# BTM7752.net
KiCad netlist of a schematic drawn in EAGLE
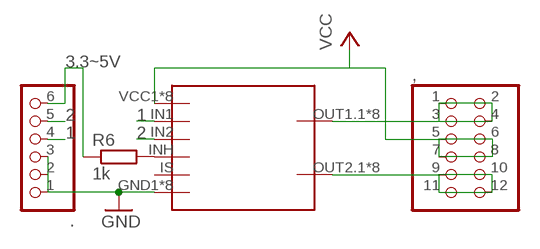
[diagram p0: schematic, sheet 1]

(export (version "E")
  (design (tool "Eeschema 10.0.6"))
  (components
    (comp (ref ",")
      (value "PINHD-2X6")
      (footprint "eagle-import:2X06")
      (libsource (lib "eagle-import") (part "PINHD-2X6"))
    )
    (comp (ref ".")
      (value "PINHD-1X6")
      (footprint "eagle-import:1X06")
      (libsource (lib "eagle-import") (part "PINHD-1X6"))
    )
    (comp (ref "R6")
      (value "1k")
      (footprint "eagle-import:R0603")
      (libsource (lib "eagle-import") (part "R-EU_R0603"))
    )
    (comp (ref "U$1")
      (value "BTM7752")
      (footprint "eagle-import:BTM7752")
      (libsource (lib "eagle-import") (part "BTM7752"))
    )
  )
  (nets
    (net (code "1") (name "/1") (class "Default")
      (node (ref ".") (pin "4") (pinfunction "4_4") (pintype "passive"))
      (node (ref "U$1") (pin "IN1") (pinfunction "IN1_IN1") (pintype "bidirectional"))
    )
    (net (code "2") (name "/2") (class "Default")
      (node (ref ".") (pin "5") (pinfunction "5_5") (pintype "passive"))
      (node (ref "U$1") (pin "IN2") (pinfunction "IN2_IN2") (pintype "bidirectional"))
    )
    (net (code "3") (name "/3.3~{5V}") (class "Default")
      (node (ref ".") (pin "6") (pinfunction "6_6") (pintype "passive"))
      (node (ref "R6") (pin "1") (pinfunction "1_1") (pintype "passive"))
    )
    (net (code "4") (name "GND") (class "Default")
      (node (ref ".") (pin "1") (pinfunction "1_1") (pintype "passive"))
      (node (ref ".") (pin "2") (pinfunction "2_2") (pintype "passive"))
      (node (ref ".") (pin "3") (pinfunction "3_3") (pintype "passive"))
      (node (ref "U$1") (pin "GND1") (pinfunction "GND_GND1") (pintype "bidirectional"))
      (node (ref "U$1") (pin "GND2") (pinfunction "GND_GND2") (pintype "bidirectional"))
      (node (ref "U$1") (pin "GND3") (pinfunction "GND_GND3") (pintype "bidirectional"))
      (node (ref "U$1") (pin "GND4") (pinfunction "GND_GND4") (pintype "bidirectional"))
      (node (ref "U$1") (pin "GND5") (pinfunction "GND_GND5") (pintype "bidirectional"))
      (node (ref "U$1") (pin "GND6") (pinfunction "GND_GND6") (pintype "bidirectional"))
      (node (ref "U$1") (pin "GND7") (pinfunction "GND_GND7") (pintype "bidirectional"))
      (node (ref "U$1") (pin "GND8") (pinfunction "GND_GND8") (pintype "bidirectional"))
    )
    (net (code "5") (name "Net-(,-Pad1)") (class "Default")
      (node (ref ",") (pin "1") (pinfunction "1_1") (pintype "passive"))
      (node (ref ",") (pin "2") (pinfunction "2_2") (pintype "passive"))
      (node (ref ",") (pin "3") (pinfunction "3_3") (pintype "passive"))
      (node (ref ",") (pin "4") (pinfunction "4_4") (pintype "passive"))
      (node (ref "U$1") (pin "OUT1.1") (pinfunction "OUT1_OUT1.1") (pintype "bidirectional"))
      (node (ref "U$1") (pin "OUT1.2") (pinfunction "OUT1_OUT1.2") (pintype "bidirectional"))
      (node (ref "U$1") (pin "OUT1.3") (pinfunction "OUT1_OUT1.3") (pintype "bidirectional"))
      (node (ref "U$1") (pin "OUT1.4") (pinfunction "OUT1_OUT1.4") (pintype "bidirectional"))
      (node (ref "U$1") (pin "OUT1.5") (pinfunction "OUT1_OUT1.5") (pintype "bidirectional"))
      (node (ref "U$1") (pin "OUT1.6") (pinfunction "OUT1_OUT1.6") (pintype "bidirectional"))
      (node (ref "U$1") (pin "OUT1.7") (pinfunction "OUT1_OUT1.7") (pintype "bidirectional"))
      (node (ref "U$1") (pin "OUT1.8") (pinfunction "OUT1_OUT1.8") (pintype "bidirectional"))
    )
    (net (code "6") (name "Net-(,-Pad10)") (class "Default")
      (node (ref ",") (pin "10") (pinfunction "10_10") (pintype "passive"))
      (node (ref ",") (pin "11") (pinfunction "11_11") (pintype "passive"))
      (node (ref ",") (pin "12") (pinfunction "12_12") (pintype "passive"))
      (node (ref ",") (pin "9") (pinfunction "9_9") (pintype "passive"))
      (node (ref "U$1") (pin "OUT2.1") (pinfunction "OUT2_OUT2.1") (pintype "bidirectional"))
      (node (ref "U$1") (pin "OUT2.2") (pinfunction "OUT2_OUT2.2") (pintype "bidirectional"))
      (node (ref "U$1") (pin "OUT2.3") (pinfunction "OUT2_OUT2.3") (pintype "bidirectional"))
      (node (ref "U$1") (pin "OUT2.4") (pinfunction "OUT2_OUT2.4") (pintype "bidirectional"))
      (node (ref "U$1") (pin "OUT2.5") (pinfunction "OUT2_OUT2.5") (pintype "bidirectional"))
      (node (ref "U$1") (pin "OUT2.6") (pinfunction "OUT2_OUT2.6") (pintype "bidirectional"))
      (node (ref "U$1") (pin "OUT2.7") (pinfunction "OUT2_OUT2.7") (pintype "bidirectional"))
      (node (ref "U$1") (pin "OUT2.8") (pinfunction "OUT2_OUT2.8") (pintype "bidirectional"))
    )
    (net (code "7") (name "Net-(R6-Pad2)") (class "Default")
      (node (ref "R6") (pin "2") (pinfunction "2_2") (pintype "passive"))
      (node (ref "U$1") (pin "INH") (pinfunction "INH_INH") (pintype "bidirectional"))
    )
    (net (code "8") (name "VCC") (class "Default")
      (node (ref ",") (pin "5") (pinfunction "5_5") (pintype "passive"))
      (node (ref ",") (pin "6") (pinfunction "6_6") (pintype "passive"))
      (node (ref ",") (pin "7") (pinfunction "7_7") (pintype "passive"))
      (node (ref ",") (pin "8") (pinfunction "8_8") (pintype "passive"))
      (node (ref "U$1") (pin "VCC1") (pinfunction "VCC_VCC1") (pintype "bidirectional"))
      (node (ref "U$1") (pin "VCC2") (pinfunction "VCC_VCC2") (pintype "bidirectional"))
      (node (ref "U$1") (pin "VCC3") (pinfunction "VCC_VCC3") (pintype "bidirectional"))
      (node (ref "U$1") (pin "VCC4") (pinfunction "VCC_VCC4") (pintype "bidirectional"))
      (node (ref "U$1") (pin "VCC5") (pinfunction "VCC_VCC5") (pintype "bidirectional"))
      (node (ref "U$1") (pin "VCC6") (pinfunction "VCC_VCC6") (pintype "bidirectional"))
      (node (ref "U$1") (pin "VCC7") (pinfunction "VCC_VCC7") (pintype "bidirectional"))
      (node (ref "U$1") (pin "VCC8") (pinfunction "VCC_VCC8") (pintype "bidirectional"))
    )
    (net (code "9") (name "unconnected-(U$1-PadIS)") (class "Default")
      (node (ref "U$1") (pin "IS") (pinfunction "IS_IS") (pintype "bidirectional"))
    )
  )
)
